# Speaker.net
KiCad netlist of a schematic drawn in Altium Designer
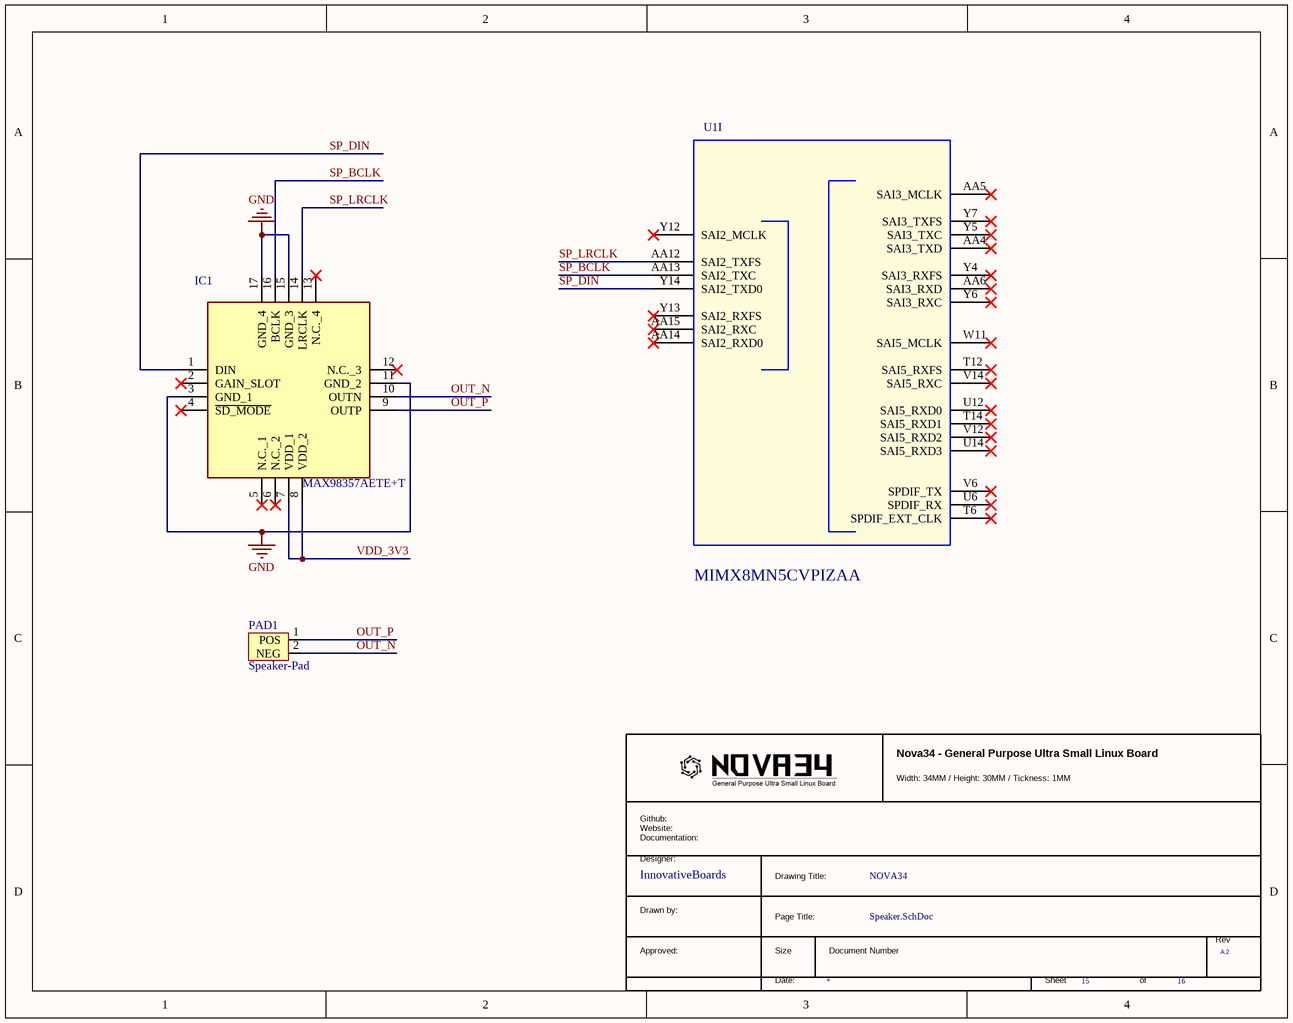
[diagram p0: Speaker.SchDoc]

(export (version "E")
  (design (tool "Eeschema 10.0.6"))
  (components
    (comp (ref "*")
      (value "TitleBlock_MCPG")
      (fields (field (name "REVCODE") "A.2"))
      (libsource (lib "Nova_SCHLIB") (part "TitleBlock_MCPG"))
    )
    (comp (ref "IC1")
      (value "MAX98357AETE+T")
      (footprint "QFN50P300X300X80-17N")
      (description "Integrated Circuit")
      (fields
        (field (name "MANUFACTURER_PART_NUMBER") "MAX98357AETE+")
        (field (name "MOUSER PART NUMBER") "700-MAX98357AETE+")
      )
      (libsource (lib "Nova_SCHLIB") (part "MAX98357AETE+"))
    )
    (comp (ref "PAD1")
      (value "Speaker-Pad")
      (footprint "Speaker-Pad")
      (libsource (lib "Nova_SCHLIB") (part "Speaker-Pad"))
    )
    (comp (ref "U1")
      (value "MIMX8MN5CVPIZAA")
      (footprint "BGA306C50P21X21_1100X1100X101")
      (description "IC CPU QUAD CORTEX A53+M7 1.4GHZ -- BGA306")
      (libsource (lib "Nova_SCHLIB") (part "MIMX8MN"))
    )
  )
  (nets
    (net (code "1") (name "/OUT_N") (class "Default")
      (node (ref "IC1") (pin "10") (pinfunction "OUTN_10") (pintype "passive"))
      (node (ref "PAD1") (pin "2") (pinfunction "NEG_2") (pintype "passive"))
    )
    (net (code "2") (name "/OUT_P") (class "Default")
      (node (ref "IC1") (pin "9") (pinfunction "OUTP_9") (pintype "passive"))
      (node (ref "PAD1") (pin "1") (pinfunction "POS_1") (pintype "passive"))
    )
    (net (code "3") (name "/SP_BCLK") (class "Default")
      (node (ref "IC1") (pin "16") (pinfunction "BCLK_16") (pintype "passive"))
      (node (ref "U1") (pin "AA13") (pinfunction "SAI2_TXC_AA13") (pintype "passive"))
    )
    (net (code "4") (name "/SP_DIN") (class "Default")
      (node (ref "IC1") (pin "1") (pinfunction "DIN_1") (pintype "passive"))
      (node (ref "U1") (pin "Y14") (pinfunction "SAI2_TXD0_Y14") (pintype "passive"))
    )
    (net (code "5") (name "/SP_LRCLK") (class "Default")
      (node (ref "IC1") (pin "14") (pinfunction "LRCLK_14") (pintype "passive"))
      (node (ref "U1") (pin "AA12") (pinfunction "SAI2_TXFS_AA12") (pintype "passive"))
    )
    (net (code "6") (name "/VDD_3V3") (class "Default")
      (node (ref "IC1") (pin "7") (pinfunction "VDD_1_7") (pintype "passive"))
      (node (ref "IC1") (pin "8") (pinfunction "VDD_2_8") (pintype "passive"))
    )
    (net (code "7") (name "GND") (class "Default")
      (node (ref "IC1") (pin "11") (pinfunction "GND_2_11") (pintype "passive"))
      (node (ref "IC1") (pin "15") (pinfunction "GND_3_15") (pintype "passive"))
      (node (ref "IC1") (pin "17") (pinfunction "GND_4_17") (pintype "passive"))
      (node (ref "IC1") (pin "3") (pinfunction "GND_1_3") (pintype "passive"))
    )
    (net (code "8") (name "unconnected-(IC1-GAIN_SLOT-Pad2)") (class "Default")
      (node (ref "IC1") (pin "2") (pinfunction "GAIN_SLOT_2") (pintype "passive+no_connect"))
    )
    (net (code "9") (name "unconnected-(IC1-N.C._1-Pad5)") (class "Default")
      (node (ref "IC1") (pin "5") (pinfunction "N.C._1_5") (pintype "passive+no_connect"))
    )
    (net (code "10") (name "unconnected-(IC1-N.C._2-Pad6)") (class "Default")
      (node (ref "IC1") (pin "6") (pinfunction "N.C._2_6") (pintype "passive+no_connect"))
    )
    (net (code "11") (name "unconnected-(IC1-N.C._3-Pad12)") (class "Default")
      (node (ref "IC1") (pin "12") (pinfunction "N.C._3_12") (pintype "passive+no_connect"))
    )
    (net (code "12") (name "unconnected-(IC1-N.C._4-Pad13)") (class "Default")
      (node (ref "IC1") (pin "13") (pinfunction "N.C._4_13") (pintype "passive+no_connect"))
    )
    (net (code "13") (name "unconnected-(IC1-~{SD_MODE}-Pad4)") (class "Default")
      (node (ref "IC1") (pin "4") (pinfunction "~{SD_MODE}_4") (pintype "passive+no_connect"))
    )
    (net (code "14") (name "unconnected-(U1I-SAI2_MCLK-PadY12)") (class "Default")
      (node (ref "U1") (pin "Y12") (pinfunction "SAI2_MCLK_Y12") (pintype "passive+no_connect"))
    )
    (net (code "15") (name "unconnected-(U1I-SAI2_RXC-PadAA15)") (class "Default")
      (node (ref "U1") (pin "AA15") (pinfunction "SAI2_RXC_AA15") (pintype "passive+no_connect"))
    )
    (net (code "16") (name "unconnected-(U1I-SAI2_RXD0-PadAA14)") (class "Default")
      (node (ref "U1") (pin "AA14") (pinfunction "SAI2_RXD0_AA14") (pintype "passive+no_connect"))
    )
    (net (code "17") (name "unconnected-(U1I-SAI2_RXFS-PadY13)") (class "Default")
      (node (ref "U1") (pin "Y13") (pinfunction "SAI2_RXFS_Y13") (pintype "passive+no_connect"))
    )
    (net (code "18") (name "unconnected-(U1I-SAI3_MCLK-PadAA5)") (class "Default")
      (node (ref "U1") (pin "AA5") (pinfunction "SAI3_MCLK_AA5") (pintype "passive+no_connect"))
    )
    (net (code "19") (name "unconnected-(U1I-SAI3_RXC-PadY6)") (class "Default")
      (node (ref "U1") (pin "Y6") (pinfunction "SAI3_RXC_Y6") (pintype "passive+no_connect"))
    )
    (net (code "20") (name "unconnected-(U1I-SAI3_RXD-PadAA6)") (class "Default")
      (node (ref "U1") (pin "AA6") (pinfunction "SAI3_RXD_AA6") (pintype "passive+no_connect"))
    )
    (net (code "21") (name "unconnected-(U1I-SAI3_RXFS-PadY4)") (class "Default")
      (node (ref "U1") (pin "Y4") (pinfunction "SAI3_RXFS_Y4") (pintype "passive+no_connect"))
    )
    (net (code "22") (name "unconnected-(U1I-SAI3_TXC-PadY5)") (class "Default")
      (node (ref "U1") (pin "Y5") (pinfunction "SAI3_TXC_Y5") (pintype "passive+no_connect"))
    )
    (net (code "23") (name "unconnected-(U1I-SAI3_TXD-PadAA4)") (class "Default")
      (node (ref "U1") (pin "AA4") (pinfunction "SAI3_TXD_AA4") (pintype "passive+no_connect"))
    )
    (net (code "24") (name "unconnected-(U1I-SAI3_TXFS-PadY7)") (class "Default")
      (node (ref "U1") (pin "Y7") (pinfunction "SAI3_TXFS_Y7") (pintype "passive+no_connect"))
    )
    (net (code "25") (name "unconnected-(U1I-SAI5_MCLK-PadW11)") (class "Default")
      (node (ref "U1") (pin "W11") (pinfunction "SAI5_MCLK_W11") (pintype "passive+no_connect"))
    )
    (net (code "26") (name "unconnected-(U1I-SAI5_RXC-PadV14)") (class "Default")
      (node (ref "U1") (pin "V14") (pinfunction "SAI5_RXC_V14") (pintype "passive+no_connect"))
    )
    (net (code "27") (name "unconnected-(U1I-SAI5_RXD0-PadU12)") (class "Default")
      (node (ref "U1") (pin "U12") (pinfunction "SAI5_RXD0_U12") (pintype "passive+no_connect"))
    )
    (net (code "28") (name "unconnected-(U1I-SAI5_RXD1-PadT14)") (class "Default")
      (node (ref "U1") (pin "T14") (pinfunction "SAI5_RXD1_T14") (pintype "passive+no_connect"))
    )
    (net (code "29") (name "unconnected-(U1I-SAI5_RXD2-PadV12)") (class "Default")
      (node (ref "U1") (pin "V12") (pinfunction "SAI5_RXD2_V12") (pintype "passive+no_connect"))
    )
    (net (code "30") (name "unconnected-(U1I-SAI5_RXD3-PadU14)") (class "Default")
      (node (ref "U1") (pin "U14") (pinfunction "SAI5_RXD3_U14") (pintype "passive+no_connect"))
    )
    (net (code "31") (name "unconnected-(U1I-SAI5_RXFS-PadT12)") (class "Default")
      (node (ref "U1") (pin "T12") (pinfunction "SAI5_RXFS_T12") (pintype "passive+no_connect"))
    )
    (net (code "32") (name "unconnected-(U1I-SPDIF_EXT_CLK-PadT6)") (class "Default")
      (node (ref "U1") (pin "T6") (pinfunction "SPDIF_EXT_CLK_T6") (pintype "passive+no_connect"))
    )
    (net (code "33") (name "unconnected-(U1I-SPDIF_RX-PadU6)") (class "Default")
      (node (ref "U1") (pin "U6") (pinfunction "SPDIF_RX_U6") (pintype "passive+no_connect"))
    )
    (net (code "34") (name "unconnected-(U1I-SPDIF_TX-PadV6)") (class "Default")
      (node (ref "U1") (pin "V6") (pinfunction "SPDIF_TX_V6") (pintype "passive+no_connect"))
    )
  )
)
